# RGB_Lamp_Project.net
KiCad netlist of a schematic drawn in EAGLE
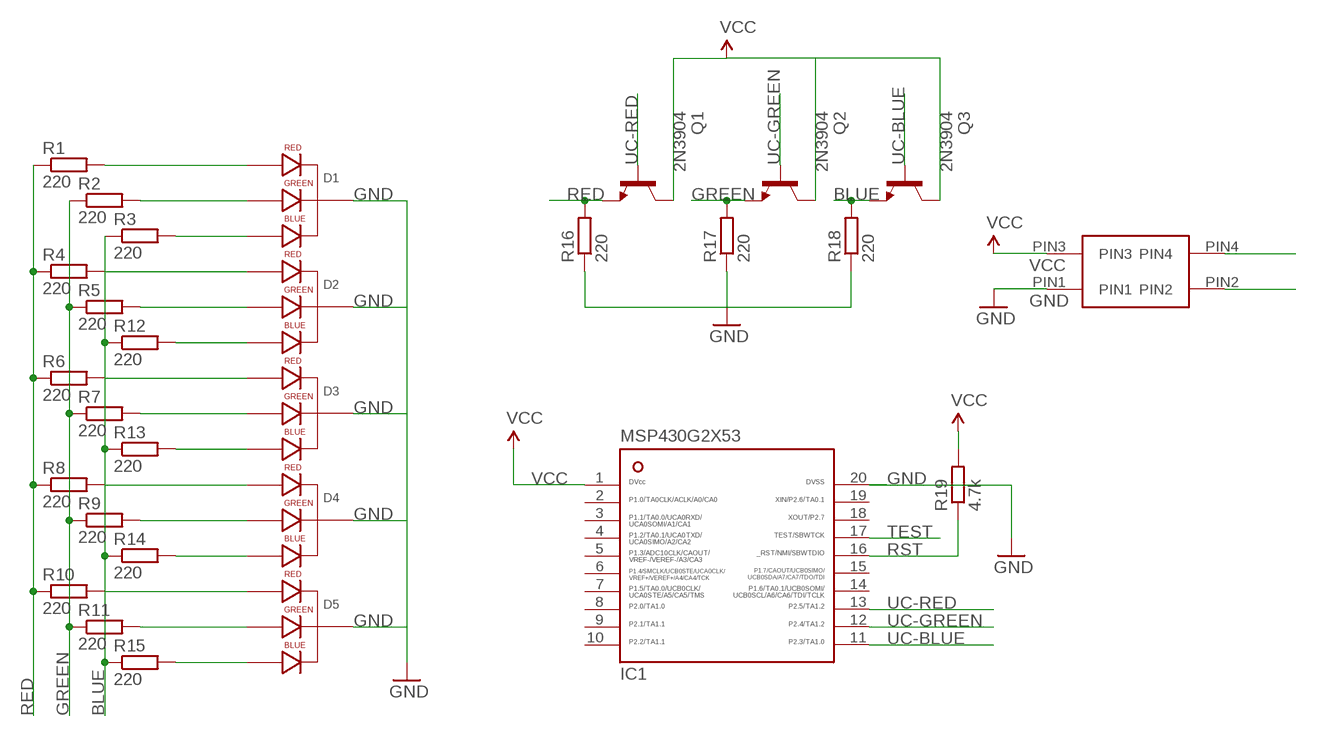
[diagram p0: schematic, sheet 1]

(export (version "E")
  (design (tool "Eeschema 10.0.6"))
  (components
    (comp (ref "D1")
      (value "LED-RGB-CC-THRUCLEAR")
      (footprint "eagle-import:LED-RGB-THRU")
      (libsource (lib "eagle-import") (part "LED-RGB-CC-THRUCLEAR"))
    )
    (comp (ref "D2")
      (value "LED-RGB-CC-THRUCLEAR")
      (footprint "eagle-import:LED-RGB-THRU")
      (libsource (lib "eagle-import") (part "LED-RGB-CC-THRUCLEAR"))
    )
    (comp (ref "D3")
      (value "LED-RGB-CC-THRUCLEAR")
      (footprint "eagle-import:LED-RGB-THRU")
      (libsource (lib "eagle-import") (part "LED-RGB-CC-THRUCLEAR"))
    )
    (comp (ref "D4")
      (value "LED-RGB-CC-THRUCLEAR")
      (footprint "eagle-import:LED-RGB-THRU")
      (libsource (lib "eagle-import") (part "LED-RGB-CC-THRUCLEAR"))
    )
    (comp (ref "D5")
      (value "LED-RGB-CC-THRUCLEAR")
      (footprint "eagle-import:LED-RGB-THRU")
      (libsource (lib "eagle-import") (part "LED-RGB-CC-THRUCLEAR"))
    )
    (comp (ref "IC1")
      (value "MSP430G2X53-20PW20")
      (footprint "eagle-import:PW20")
      (libsource (lib "eagle-import") (part "MSP430G2X53-20PW20"))
    )
    (comp (ref "Q1")
      (value "2N3904")
      (footprint "eagle-import:TO92")
      (libsource (lib "eagle-import") (part "2N3904"))
    )
    (comp (ref "Q2")
      (value "2N3904")
      (footprint "eagle-import:TO92")
      (libsource (lib "eagle-import") (part "2N3904"))
    )
    (comp (ref "Q3")
      (value "2N3904")
      (footprint "eagle-import:TO92")
      (libsource (lib "eagle-import") (part "2N3904"))
    )
    (comp (ref "R1")
      (value "220")
      (footprint "eagle-import:R0805")
      (libsource (lib "eagle-import") (part "R-EU_R0805"))
    )
    (comp (ref "R2")
      (value "220")
      (footprint "eagle-import:R0805")
      (libsource (lib "eagle-import") (part "R-EU_R0805"))
    )
    (comp (ref "R3")
      (value "220")
      (footprint "eagle-import:R0805")
      (libsource (lib "eagle-import") (part "R-EU_R0805"))
    )
    (comp (ref "R4")
      (value "220")
      (footprint "eagle-import:R0805")
      (libsource (lib "eagle-import") (part "R-EU_R0805"))
    )
    (comp (ref "R5")
      (value "220")
      (footprint "eagle-import:R0805")
      (libsource (lib "eagle-import") (part "R-EU_R0805"))
    )
    (comp (ref "R6")
      (value "220")
      (footprint "eagle-import:R0805")
      (libsource (lib "eagle-import") (part "R-EU_R0805"))
    )
    (comp (ref "R7")
      (value "220")
      (footprint "eagle-import:R0805")
      (libsource (lib "eagle-import") (part "R-EU_R0805"))
    )
    (comp (ref "R8")
      (value "220")
      (footprint "eagle-import:R0805")
      (libsource (lib "eagle-import") (part "R-EU_R0805"))
    )
    (comp (ref "R9")
      (value "220")
      (footprint "eagle-import:R0805")
      (libsource (lib "eagle-import") (part "R-EU_R0805"))
    )
    (comp (ref "R10")
      (value "220")
      (footprint "eagle-import:R0805")
      (libsource (lib "eagle-import") (part "R-EU_R0805"))
    )
    (comp (ref "R11")
      (value "220")
      (footprint "eagle-import:R0805")
      (libsource (lib "eagle-import") (part "R-EU_R0805"))
    )
    (comp (ref "R12")
      (value "220")
      (footprint "eagle-import:R0805")
      (libsource (lib "eagle-import") (part "R-EU_R0805"))
    )
    (comp (ref "R13")
      (value "220")
      (footprint "eagle-import:R0805")
      (libsource (lib "eagle-import") (part "R-EU_R0805"))
    )
    (comp (ref "R14")
      (value "220")
      (footprint "eagle-import:R0805")
      (libsource (lib "eagle-import") (part "R-EU_R0805"))
    )
    (comp (ref "R15")
      (value "220")
      (footprint "eagle-import:R0805")
      (libsource (lib "eagle-import") (part "R-EU_R0805"))
    )
    (comp (ref "R16")
      (value "220")
      (footprint "eagle-import:R0805")
      (libsource (lib "eagle-import") (part "R-EU_R0805"))
    )
    (comp (ref "R17")
      (value "220")
      (footprint "eagle-import:R0805")
      (libsource (lib "eagle-import") (part "R-EU_R0805"))
    )
    (comp (ref "R18")
      (value "220")
      (footprint "eagle-import:R0805")
      (libsource (lib "eagle-import") (part "R-EU_R0805"))
    )
    (comp (ref "R19")
      (value "4.7k")
      (footprint "eagle-import:R0805")
      (libsource (lib "eagle-import") (part "R-EU_R0805"))
    )
    (comp (ref "U$1")
      (value "PINHEADER-2X2-SMD")
      (footprint "eagle-import:PINHEADER-2X2-SMD")
      (libsource (lib "eagle-import") (part "PINHEADER-2X2-SMD"))
    )
  )
  (nets
    (net (code "1") (name "/BLUE") (class "Default")
      (node (ref "Q3") (pin "3") (pinfunction "E_3") (pintype "passive"))
      (node (ref "R12") (pin "1") (pinfunction "1_1") (pintype "passive"))
      (node (ref "R13") (pin "1") (pinfunction "1_1") (pintype "passive"))
      (node (ref "R14") (pin "1") (pinfunction "1_1") (pintype "passive"))
      (node (ref "R15") (pin "1") (pinfunction "1_1") (pintype "passive"))
      (node (ref "R18") (pin "2") (pinfunction "2_2") (pintype "passive"))
      (node (ref "R3") (pin "1") (pinfunction "1_1") (pintype "passive"))
    )
    (net (code "2") (name "/GREEN") (class "Default")
      (node (ref "Q2") (pin "3") (pinfunction "E_3") (pintype "passive"))
      (node (ref "R11") (pin "1") (pinfunction "1_1") (pintype "passive"))
      (node (ref "R17") (pin "2") (pinfunction "2_2") (pintype "passive"))
      (node (ref "R2") (pin "1") (pinfunction "1_1") (pintype "passive"))
      (node (ref "R5") (pin "1") (pinfunction "1_1") (pintype "passive"))
      (node (ref "R7") (pin "1") (pinfunction "1_1") (pintype "passive"))
      (node (ref "R9") (pin "1") (pinfunction "1_1") (pintype "passive"))
    )
    (net (code "3") (name "/RED") (class "Default")
      (node (ref "Q1") (pin "3") (pinfunction "E_3") (pintype "passive"))
      (node (ref "R1") (pin "1") (pinfunction "1_1") (pintype "passive"))
      (node (ref "R10") (pin "1") (pinfunction "1_1") (pintype "passive"))
      (node (ref "R16") (pin "2") (pinfunction "2_2") (pintype "passive"))
      (node (ref "R4") (pin "1") (pinfunction "1_1") (pintype "passive"))
      (node (ref "R6") (pin "1") (pinfunction "1_1") (pintype "passive"))
      (node (ref "R8") (pin "1") (pinfunction "1_1") (pintype "passive"))
    )
    (net (code "4") (name "/RST") (class "Default")
      (node (ref "IC1") (pin "16") (pinfunction "16_16") (pintype "bidirectional"))
      (node (ref "R19") (pin "1") (pinfunction "1_1") (pintype "passive"))
      (node (ref "U$1") (pin "PIN4") (pinfunction "PIN4_PIN4") (pintype "bidirectional"))
    )
    (net (code "5") (name "/TEST") (class "Default")
      (node (ref "IC1") (pin "17") (pinfunction "17_17") (pintype "bidirectional"))
      (node (ref "U$1") (pin "PIN2") (pinfunction "PIN2_PIN2") (pintype "bidirectional"))
    )
    (net (code "6") (name "/UC-BLUE") (class "Default")
      (node (ref "IC1") (pin "11") (pinfunction "11_11") (pintype "bidirectional"))
      (node (ref "Q3") (pin "2") (pinfunction "B_2") (pintype "passive"))
    )
    (net (code "7") (name "/UC-GREEN") (class "Default")
      (node (ref "IC1") (pin "12") (pinfunction "12_12") (pintype "bidirectional"))
      (node (ref "Q2") (pin "2") (pinfunction "B_2") (pintype "passive"))
    )
    (net (code "8") (name "/UC-RED") (class "Default")
      (node (ref "IC1") (pin "13") (pinfunction "13_13") (pintype "bidirectional"))
      (node (ref "Q1") (pin "2") (pinfunction "B_2") (pintype "passive"))
    )
    (net (code "9") (name "GND") (class "Default")
      (node (ref "D1") (pin "2") (pinfunction "CATHODE_2") (pintype "bidirectional"))
      (node (ref "D2") (pin "2") (pinfunction "CATHODE_2") (pintype "bidirectional"))
      (node (ref "D3") (pin "2") (pinfunction "CATHODE_2") (pintype "bidirectional"))
      (node (ref "D4") (pin "2") (pinfunction "CATHODE_2") (pintype "bidirectional"))
      (node (ref "D5") (pin "2") (pinfunction "CATHODE_2") (pintype "bidirectional"))
      (node (ref "IC1") (pin "20") (pinfunction "20_20") (pintype "bidirectional"))
      (node (ref "R16") (pin "1") (pinfunction "1_1") (pintype "passive"))
      (node (ref "R17") (pin "1") (pinfunction "1_1") (pintype "passive"))
      (node (ref "R18") (pin "1") (pinfunction "1_1") (pintype "passive"))
      (node (ref "U$1") (pin "PIN1") (pinfunction "PIN1_PIN1") (pintype "bidirectional"))
    )
    (net (code "10") (name "Net-(D1-BLUE_CATHODE)") (class "Default")
      (node (ref "D1") (pin "4") (pinfunction "BLUE_CATHODE_4") (pintype "bidirectional"))
      (node (ref "R3") (pin "2") (pinfunction "2_2") (pintype "passive"))
    )
    (net (code "11") (name "Net-(D1-GREEN_CATHODE)") (class "Default")
      (node (ref "D1") (pin "3") (pinfunction "GREEN_CATHODE_3") (pintype "bidirectional"))
      (node (ref "R2") (pin "2") (pinfunction "2_2") (pintype "passive"))
    )
    (net (code "12") (name "Net-(D1-RED_CATHODE)") (class "Default")
      (node (ref "D1") (pin "1") (pinfunction "RED_CATHODE_1") (pintype "bidirectional"))
      (node (ref "R1") (pin "2") (pinfunction "2_2") (pintype "passive"))
    )
    (net (code "13") (name "Net-(D2-BLUE_CATHODE)") (class "Default")
      (node (ref "D2") (pin "4") (pinfunction "BLUE_CATHODE_4") (pintype "bidirectional"))
      (node (ref "R12") (pin "2") (pinfunction "2_2") (pintype "passive"))
    )
    (net (code "14") (name "Net-(D2-GREEN_CATHODE)") (class "Default")
      (node (ref "D2") (pin "3") (pinfunction "GREEN_CATHODE_3") (pintype "bidirectional"))
      (node (ref "R5") (pin "2") (pinfunction "2_2") (pintype "passive"))
    )
    (net (code "15") (name "Net-(D2-RED_CATHODE)") (class "Default")
      (node (ref "D2") (pin "1") (pinfunction "RED_CATHODE_1") (pintype "bidirectional"))
      (node (ref "R4") (pin "2") (pinfunction "2_2") (pintype "passive"))
    )
    (net (code "16") (name "Net-(D3-BLUE_CATHODE)") (class "Default")
      (node (ref "D3") (pin "4") (pinfunction "BLUE_CATHODE_4") (pintype "bidirectional"))
      (node (ref "R13") (pin "2") (pinfunction "2_2") (pintype "passive"))
    )
    (net (code "17") (name "Net-(D3-GREEN_CATHODE)") (class "Default")
      (node (ref "D3") (pin "3") (pinfunction "GREEN_CATHODE_3") (pintype "bidirectional"))
      (node (ref "R7") (pin "2") (pinfunction "2_2") (pintype "passive"))
    )
    (net (code "18") (name "Net-(D3-RED_CATHODE)") (class "Default")
      (node (ref "D3") (pin "1") (pinfunction "RED_CATHODE_1") (pintype "bidirectional"))
      (node (ref "R6") (pin "2") (pinfunction "2_2") (pintype "passive"))
    )
    (net (code "19") (name "Net-(D4-BLUE_CATHODE)") (class "Default")
      (node (ref "D4") (pin "4") (pinfunction "BLUE_CATHODE_4") (pintype "bidirectional"))
      (node (ref "R14") (pin "2") (pinfunction "2_2") (pintype "passive"))
    )
    (net (code "20") (name "Net-(D4-GREEN_CATHODE)") (class "Default")
      (node (ref "D4") (pin "3") (pinfunction "GREEN_CATHODE_3") (pintype "bidirectional"))
      (node (ref "R9") (pin "2") (pinfunction "2_2") (pintype "passive"))
    )
    (net (code "21") (name "Net-(D4-RED_CATHODE)") (class "Default")
      (node (ref "D4") (pin "1") (pinfunction "RED_CATHODE_1") (pintype "bidirectional"))
      (node (ref "R8") (pin "2") (pinfunction "2_2") (pintype "passive"))
    )
    (net (code "22") (name "Net-(D5-BLUE_CATHODE)") (class "Default")
      (node (ref "D5") (pin "4") (pinfunction "BLUE_CATHODE_4") (pintype "bidirectional"))
      (node (ref "R15") (pin "2") (pinfunction "2_2") (pintype "passive"))
    )
    (net (code "23") (name "Net-(D5-GREEN_CATHODE)") (class "Default")
      (node (ref "D5") (pin "3") (pinfunction "GREEN_CATHODE_3") (pintype "bidirectional"))
      (node (ref "R11") (pin "2") (pinfunction "2_2") (pintype "passive"))
    )
    (net (code "24") (name "Net-(D5-RED_CATHODE)") (class "Default")
      (node (ref "D5") (pin "1") (pinfunction "RED_CATHODE_1") (pintype "bidirectional"))
      (node (ref "R10") (pin "2") (pinfunction "2_2") (pintype "passive"))
    )
    (net (code "25") (name "VCC") (class "Default")
      (node (ref "IC1") (pin "1") (pinfunction "1_1") (pintype "bidirectional"))
      (node (ref "Q1") (pin "1") (pinfunction "C_1") (pintype "passive"))
      (node (ref "Q2") (pin "1") (pinfunction "C_1") (pintype "passive"))
      (node (ref "Q3") (pin "1") (pinfunction "C_1") (pintype "passive"))
      (node (ref "R19") (pin "2") (pinfunction "2_2") (pintype "passive"))
      (node (ref "U$1") (pin "PIN3") (pinfunction "PIN3_PIN3") (pintype "bidirectional"))
    )
    (net (code "26") (name "unconnected-(IC1-Pad2)") (class "Default")
      (node (ref "IC1") (pin "2") (pinfunction "2_2") (pintype "bidirectional"))
    )
    (net (code "27") (name "unconnected-(IC1-Pad3)") (class "Default")
      (node (ref "IC1") (pin "3") (pinfunction "3_3") (pintype "bidirectional"))
    )
    (net (code "28") (name "unconnected-(IC1-Pad4)") (class "Default")
      (node (ref "IC1") (pin "4") (pinfunction "4_4") (pintype "bidirectional"))
    )
    (net (code "29") (name "unconnected-(IC1-Pad5)") (class "Default")
      (node (ref "IC1") (pin "5") (pinfunction "5_5") (pintype "bidirectional"))
    )
    (net (code "30") (name "unconnected-(IC1-Pad6)") (class "Default")
      (node (ref "IC1") (pin "6") (pinfunction "6_6") (pintype "bidirectional"))
    )
    (net (code "31") (name "unconnected-(IC1-Pad7)") (class "Default")
      (node (ref "IC1") (pin "7") (pinfunction "7_7") (pintype "bidirectional"))
    )
    (net (code "32") (name "unconnected-(IC1-Pad8)") (class "Default")
      (node (ref "IC1") (pin "8") (pinfunction "8_8") (pintype "bidirectional"))
    )
    (net (code "33") (name "unconnected-(IC1-Pad9)") (class "Default")
      (node (ref "IC1") (pin "9") (pinfunction "9_9") (pintype "bidirectional"))
    )
    (net (code "34") (name "unconnected-(IC1-Pad10)") (class "Default")
      (node (ref "IC1") (pin "10") (pinfunction "10_10") (pintype "bidirectional"))
    )
    (net (code "35") (name "unconnected-(IC1-Pad14)") (class "Default")
      (node (ref "IC1") (pin "14") (pinfunction "14_14") (pintype "bidirectional"))
    )
    (net (code "36") (name "unconnected-(IC1-Pad15)") (class "Default")
      (node (ref "IC1") (pin "15") (pinfunction "15_15") (pintype "bidirectional"))
    )
    (net (code "37") (name "unconnected-(IC1-Pad18)") (class "Default")
      (node (ref "IC1") (pin "18") (pinfunction "18_18") (pintype "bidirectional"))
    )
    (net (code "38") (name "unconnected-(IC1-Pad19)") (class "Default")
      (node (ref "IC1") (pin "19") (pinfunction "19_19") (pintype "bidirectional"))
    )
  )
)
